# c8t61.net
KiCad netlist of a schematic drawn in Altium Designer
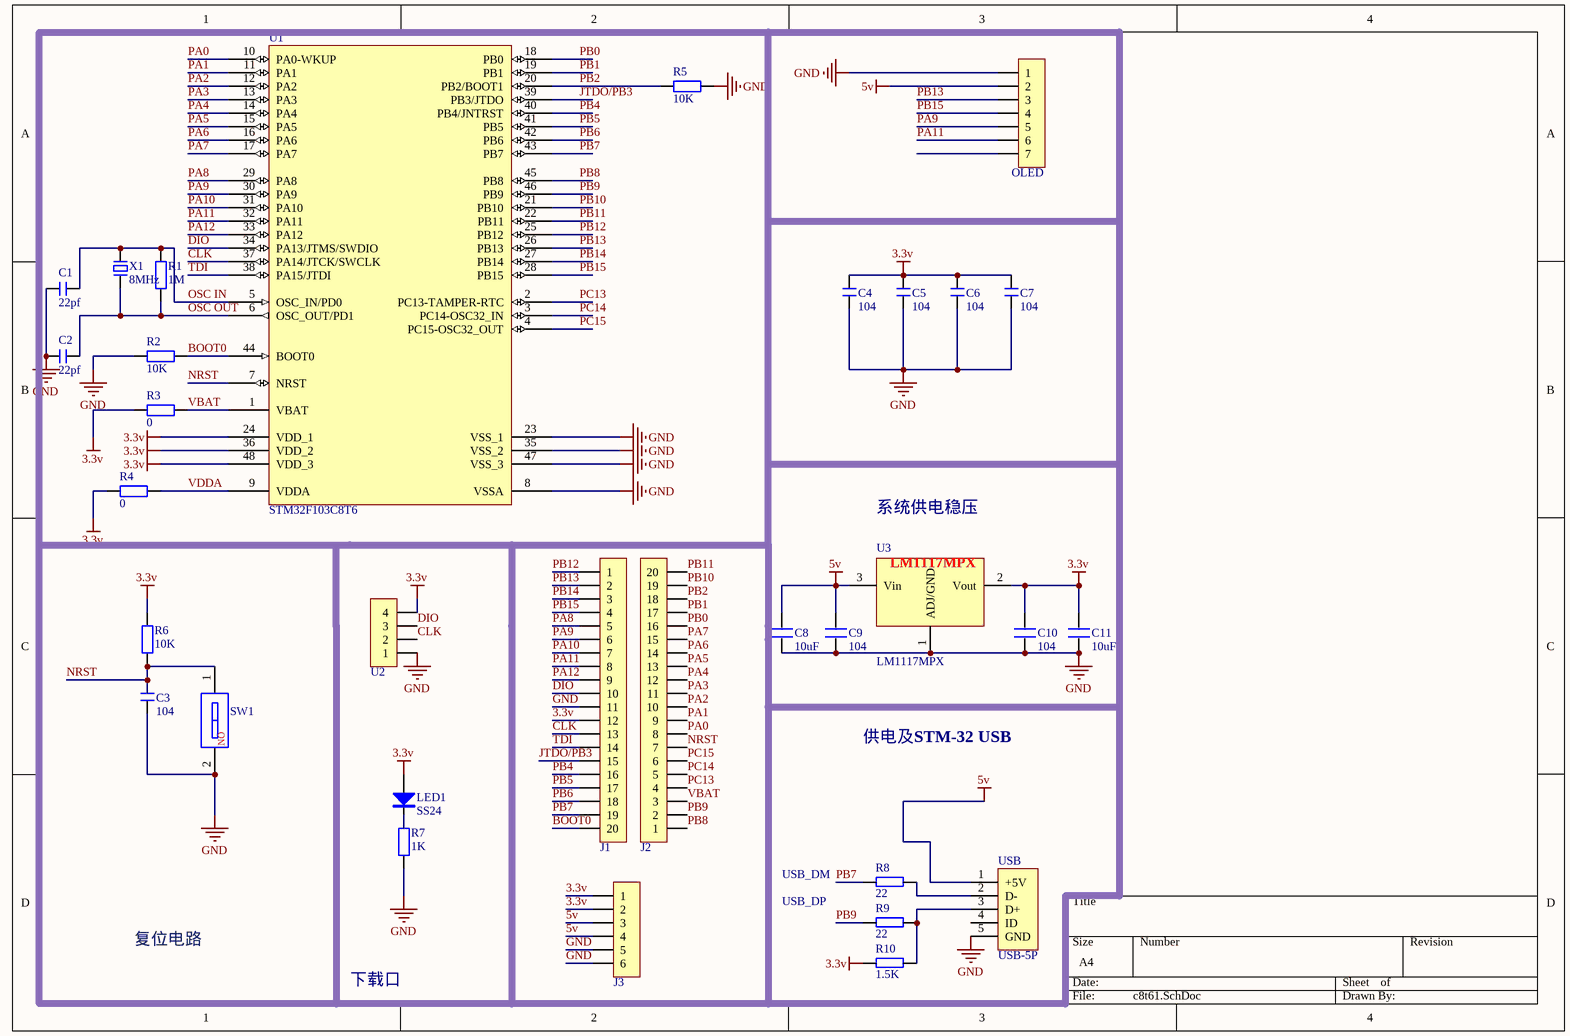
[diagram p0: c8t61.SchDoc]

(export (version "E")
  (design (tool "Eeschema 10.0.6"))
  (components
    (comp (ref "C1")
      (value "22pf")
      (footprint "C 0603")
      (description "无极性贴片电容")
      (fields (field (name "版权归属") "源创客"))
      (libsource (lib "电阻-电容-电感") (part "C"))
    )
    (comp (ref "C2")
      (value "22pf")
      (footprint "C 0603")
      (description "无极性贴片电容")
      (fields (field (name "版权归属") "源创客"))
      (libsource (lib "电阻-电容-电感") (part "C"))
    )
    (comp (ref "C3")
      (value "104")
      (footprint "C 0603")
      (description "无极性贴片电容")
      (fields (field (name "版权归属") "源创客"))
      (libsource (lib "电阻-电容-电感") (part "C"))
    )
    (comp (ref "C4")
      (value "104")
      (footprint "C 0603")
      (description "无极性贴片电容")
      (fields (field (name "版权归属") "源创客"))
      (libsource (lib "电阻-电容-电感") (part "C"))
    )
    (comp (ref "C5")
      (value "104")
      (footprint "C 0603")
      (description "无极性贴片电容")
      (fields (field (name "版权归属") "源创客"))
      (libsource (lib "电阻-电容-电感") (part "C"))
    )
    (comp (ref "C6")
      (value "104")
      (footprint "C 0603")
      (description "无极性贴片电容")
      (fields (field (name "版权归属") "源创客"))
      (libsource (lib "电阻-电容-电感") (part "C"))
    )
    (comp (ref "C7")
      (value "104")
      (footprint "C 0603")
      (description "无极性贴片电容")
      (fields (field (name "版权归属") "源创客"))
      (libsource (lib "电阻-电容-电感") (part "C"))
    )
    (comp (ref "C8") (value "10uF") (footprint "C 0805") (libsource (lib "战舰STM32开发板底板封装库") (part "C")))
    (comp (ref "C9") (value "104") (footprint "C 0805") (libsource (lib "战舰STM32开发板底板封装库") (part "C")))
    (comp (ref "C10") (value "104") (footprint "C 0805") (libsource (lib "战舰STM32开发板底板封装库") (part "C")))
    (comp (ref "C11") (value "10uF") (footprint "C 0805") (libsource (lib "战舰STM32开发板底板封装库") (part "C")))
    (comp (ref "J1")
      (value "HDR-1X20")
      (footprint "HDR-1X20")
      (description "20P接插件")
      (fields (field (name "版权归属") "源创客"))
      (libsource (lib "接插件") (part "Header 20"))
    )
    (comp (ref "J2")
      (value "HDR-1X20")
      (footprint "HDR-1X20")
      (description "20P接插件")
      (fields (field (name "版权归属") "源创客"))
      (libsource (lib "") (part "Header 20_1"))
    )
    (comp (ref "J3")
      (value "HDR-1X6")
      (footprint "HDR-1X6")
      (description "6P接插件")
      (fields (field (name "版权归属") "源创客"))
      (libsource (lib "接插件") (part "Header 6"))
    )
    (comp (ref "LED1")
      (value "SS24")
      (footprint "LED 1206G")
      (description "肖特基二极管")
      (fields (field (name "版权归属") "源创客"))
      (libsource (lib "二极管-整流桥") (part "SS24"))
    )
    (comp (ref "OLED")
      (value "HDR-1X7")
      (footprint "HDR-1X7")
      (description "7P接插件")
      (fields (field (name "版权归属") "源创客"))
      (libsource (lib "接插件") (part "Header 7"))
    )
    (comp (ref "R1")
      (value "1M")
      (footprint "R 0603")
      (description "贴片电阻")
      (fields (field (name "版权归属") "源创客"))
      (libsource (lib "电阻-电容-电感") (part "R"))
    )
    (comp (ref "R2")
      (value "10K")
      (footprint "R 0603")
      (description "贴片电阻")
      (fields (field (name "版权归属") "源创客"))
      (libsource (lib "电阻-电容-电感") (part "R"))
    )
    (comp (ref "R3")
      (value "0")
      (footprint "R 0603")
      (description "贴片电阻")
      (fields (field (name "版权归属") "源创客"))
      (libsource (lib "电阻-电容-电感") (part "R"))
    )
    (comp (ref "R4")
      (value "0")
      (footprint "R 0603")
      (description "贴片电阻")
      (fields (field (name "版权归属") "源创客"))
      (libsource (lib "电阻-电容-电感") (part "R"))
    )
    (comp (ref "R5")
      (value "10K")
      (footprint "R 0603")
      (description "贴片电阻")
      (fields (field (name "版权归属") "源创客"))
      (libsource (lib "电阻-电容-电感") (part "R"))
    )
    (comp (ref "R6")
      (value "10K")
      (footprint "R 0603")
      (description "贴片电阻")
      (fields (field (name "版权归属") "源创客"))
      (libsource (lib "电阻-电容-电感") (part "R"))
    )
    (comp (ref "R7")
      (value "1K")
      (footprint "R 0603")
      (description "贴片电阻")
      (fields (field (name "版权归属") "源创客"))
      (libsource (lib "电阻-电容-电感") (part "R"))
    )
    (comp (ref "R8") (value "22") (footprint "R 0805") (libsource (lib "战舰STM32开发板底板封装库") (part "R")))
    (comp (ref "R9") (value "22") (footprint "R 0805") (libsource (lib "战舰STM32开发板底板封装库") (part "R")))
    (comp (ref "R10") (value "1.5K") (footprint "R 0805") (libsource (lib "战舰STM32开发板底板封装库") (part "R")))
    (comp (ref "SW1")
      (value "CSW-1P")
      (footprint "TSW SMD-3*6*5")
      (description "2路编码开关")
      (fields (field (name "版权归属") "源创客"))
      (libsource (lib "按键-开关") (part "CSW-1P"))
    )
    (comp (ref "U1")
      (value "STM32F103C8T6")
      (footprint "LQFP48 7X7_M")
      (description "Flaah:64/RAM:20/IO:36")
      (fields (field (name "版权归属") "源创客"))
      (libsource (lib "STM32系列单片机") (part "STM32F103C8T6"))
    )
    (comp (ref "U2")
      (value "HDR-1X4")
      (footprint "HDR-1X4")
      (description "4P接插件")
      (fields (field (name "版权归属") "源创客"))
      (libsource (lib "接插件") (part "Header 4"))
    )
    (comp (ref "U3")
      (value "LM1117MPX")
      (footprint "SOT-223-4")
      (description "NS 800mA Low-Dropout Linear Regulator")
      (libsource (lib "电源管理") (part "LM1117MPX"))
    )
    (comp (ref "USB")
      (value "USB-5P")
      (footprint "USB-MICRO_A")
      (description "微型USB母座")
      (fields (field (name "版权归属") "源创客"))
      (libsource (lib "接口类") (part "USB-5P"))
    )
    (comp (ref "X1")
      (value "8MHz")
      (footprint "SMD5032-2")
      (description "2脚晶振")
      (fields (field (name "版权归属") "源创客"))
      (libsource (lib "保险丝-晶振") (part "XTAL-2"))
    )
  )
  (nets
    (net (code "1") (name "/BOOT0") (class "Default")
      (node (ref "J1") (pin "20") (pinfunction "20_20") (pintype "passive"))
      (node (ref "R2") (pin "1") (pinfunction "1_1") (pintype "passive"))
      (node (ref "U1") (pin "44") (pinfunction "BOOT0_44") (pintype "input"))
    )
    (net (code "2") (name "/CLK") (class "Default")
      (node (ref "J1") (pin "13") (pinfunction "13_13") (pintype "passive"))
      (node (ref "U1") (pin "37") (pinfunction "PA14/JTCK/SWCLK_37") (pintype "bidirectional"))
      (node (ref "U2") (pin "2") (pinfunction "2_2") (pintype "passive"))
    )
    (net (code "3") (name "/DIO") (class "Default")
      (node (ref "J1") (pin "10") (pinfunction "10_10") (pintype "passive"))
      (node (ref "U1") (pin "34") (pinfunction "PA13/JTMS/SWDIO_34") (pintype "bidirectional"))
      (node (ref "U2") (pin "3") (pinfunction "3_3") (pintype "passive"))
    )
    (net (code "4") (name "/JTDO{slash}PB3") (class "Default")
      (node (ref "J1") (pin "15") (pinfunction "15_15") (pintype "passive"))
      (node (ref "U1") (pin "39") (pinfunction "PB3/JTDO_39") (pintype "bidirectional"))
    )
    (net (code "5") (name "/NRST") (class "Default")
      (node (ref "C3") (pin "2") (pinfunction "2_2") (pintype "passive"))
      (node (ref "J2") (pin "7") (pinfunction "7_7") (pintype "passive"))
      (node (ref "R6") (pin "2") (pinfunction "2_2") (pintype "passive"))
      (node (ref "SW1") (pin "1") (pinfunction "1_1") (pintype "passive"))
      (node (ref "U1") (pin "7") (pinfunction "NRST_7") (pintype "bidirectional"))
    )
    (net (code "6") (name "/OSC IN") (class "Default")
      (node (ref "C1") (pin "2") (pinfunction "2_2") (pintype "passive"))
      (node (ref "R1") (pin "2") (pinfunction "2_2") (pintype "passive"))
      (node (ref "U1") (pin "5") (pinfunction "OSC_IN/PD0_5") (pintype "input"))
      (node (ref "X1") (pin "2") (pinfunction "2_2") (pintype "passive"))
    )
    (net (code "7") (name "/OSC OUT") (class "Default")
      (node (ref "C2") (pin "2") (pinfunction "2_2") (pintype "passive"))
      (node (ref "R1") (pin "1") (pinfunction "1_1") (pintype "passive"))
      (node (ref "U1") (pin "6") (pinfunction "OSC_OUT/PD1_6") (pintype "output"))
      (node (ref "X1") (pin "1") (pinfunction "1_1") (pintype "passive"))
    )
    (net (code "8") (name "/PA0") (class "Default")
      (node (ref "J2") (pin "8") (pinfunction "8_8") (pintype "passive"))
      (node (ref "U1") (pin "10") (pinfunction "PA0-WKUP_10") (pintype "bidirectional"))
    )
    (net (code "9") (name "/PA1") (class "Default")
      (node (ref "J2") (pin "9") (pinfunction "9_9") (pintype "passive"))
      (node (ref "U1") (pin "11") (pinfunction "PA1_11") (pintype "bidirectional"))
    )
    (net (code "10") (name "/PA2") (class "Default")
      (node (ref "J2") (pin "10") (pinfunction "10_10") (pintype "passive"))
      (node (ref "U1") (pin "12") (pinfunction "PA2_12") (pintype "bidirectional"))
    )
    (net (code "11") (name "/PA3") (class "Default")
      (node (ref "J2") (pin "11") (pinfunction "11_11") (pintype "passive"))
      (node (ref "U1") (pin "13") (pinfunction "PA3_13") (pintype "bidirectional"))
    )
    (net (code "12") (name "/PA4") (class "Default")
      (node (ref "J2") (pin "12") (pinfunction "12_12") (pintype "passive"))
      (node (ref "U1") (pin "14") (pinfunction "PA4_14") (pintype "bidirectional"))
    )
    (net (code "13") (name "/PA5") (class "Default")
      (node (ref "J2") (pin "13") (pinfunction "13_13") (pintype "passive"))
      (node (ref "U1") (pin "15") (pinfunction "PA5_15") (pintype "bidirectional"))
    )
    (net (code "14") (name "/PA6") (class "Default")
      (node (ref "J2") (pin "14") (pinfunction "14_14") (pintype "passive"))
      (node (ref "U1") (pin "16") (pinfunction "PA6_16") (pintype "bidirectional"))
    )
    (net (code "15") (name "/PA7") (class "Default")
      (node (ref "J2") (pin "15") (pinfunction "15_15") (pintype "passive"))
      (node (ref "U1") (pin "17") (pinfunction "PA7_17") (pintype "bidirectional"))
    )
    (net (code "16") (name "/PA8") (class "Default")
      (node (ref "J1") (pin "5") (pinfunction "5_5") (pintype "passive"))
      (node (ref "U1") (pin "29") (pinfunction "PA8_29") (pintype "bidirectional"))
    )
    (net (code "17") (name "/PA9") (class "Default")
      (node (ref "J1") (pin "6") (pinfunction "6_6") (pintype "passive"))
      (node (ref "OLED") (pin "5") (pinfunction "5_5") (pintype "passive"))
      (node (ref "U1") (pin "30") (pinfunction "PA9_30") (pintype "bidirectional"))
    )
    (net (code "18") (name "/PA10") (class "Default")
      (node (ref "J1") (pin "7") (pinfunction "7_7") (pintype "passive"))
      (node (ref "U1") (pin "31") (pinfunction "PA10_31") (pintype "bidirectional"))
    )
    (net (code "19") (name "/PA11") (class "Default")
      (node (ref "J1") (pin "8") (pinfunction "8_8") (pintype "passive"))
      (node (ref "OLED") (pin "6") (pinfunction "6_6") (pintype "passive"))
      (node (ref "U1") (pin "32") (pinfunction "PA11_32") (pintype "bidirectional"))
    )
    (net (code "20") (name "/PA12") (class "Default")
      (node (ref "J1") (pin "9") (pinfunction "9_9") (pintype "passive"))
      (node (ref "U1") (pin "33") (pinfunction "PA12_33") (pintype "bidirectional"))
    )
    (net (code "21") (name "/PB0") (class "Default")
      (node (ref "J2") (pin "16") (pinfunction "16_16") (pintype "passive"))
      (node (ref "U1") (pin "18") (pinfunction "PB0_18") (pintype "bidirectional"))
    )
    (net (code "22") (name "/PB1") (class "Default")
      (node (ref "J2") (pin "17") (pinfunction "17_17") (pintype "passive"))
      (node (ref "U1") (pin "19") (pinfunction "PB1_19") (pintype "bidirectional"))
    )
    (net (code "23") (name "/PB2") (class "Default")
      (node (ref "J2") (pin "18") (pinfunction "18_18") (pintype "passive"))
      (node (ref "R5") (pin "2") (pinfunction "2_2") (pintype "passive"))
      (node (ref "U1") (pin "20") (pinfunction "PB2/BOOT1_20") (pintype "bidirectional"))
    )
    (net (code "24") (name "/PB4") (class "Default")
      (node (ref "J1") (pin "16") (pinfunction "16_16") (pintype "passive"))
      (node (ref "U1") (pin "40") (pinfunction "PB4/JNTRST_40") (pintype "bidirectional"))
    )
    (net (code "25") (name "/PB5") (class "Default")
      (node (ref "J1") (pin "17") (pinfunction "17_17") (pintype "passive"))
      (node (ref "U1") (pin "41") (pinfunction "PB5_41") (pintype "bidirectional"))
    )
    (net (code "26") (name "/PB6") (class "Default")
      (node (ref "J1") (pin "18") (pinfunction "18_18") (pintype "passive"))
      (node (ref "U1") (pin "42") (pinfunction "PB6_42") (pintype "bidirectional"))
    )
    (net (code "27") (name "/PB7") (class "Default")
      (node (ref "J1") (pin "19") (pinfunction "19_19") (pintype "passive"))
      (node (ref "R8") (pin "2") (pintype "passive"))
      (node (ref "U1") (pin "43") (pinfunction "PB7_43") (pintype "bidirectional"))
    )
    (net (code "28") (name "/PB8") (class "Default")
      (node (ref "J2") (pin "1") (pinfunction "1_1") (pintype "passive"))
      (node (ref "U1") (pin "45") (pinfunction "PB8_45") (pintype "bidirectional"))
    )
    (net (code "29") (name "/PB9") (class "Default")
      (node (ref "J2") (pin "2") (pinfunction "2_2") (pintype "passive"))
      (node (ref "R9") (pin "2") (pintype "passive"))
      (node (ref "U1") (pin "46") (pinfunction "PB9_46") (pintype "bidirectional"))
    )
    (net (code "30") (name "/PB10") (class "Default")
      (node (ref "J2") (pin "19") (pinfunction "19_19") (pintype "passive"))
      (node (ref "U1") (pin "21") (pinfunction "PB10_21") (pintype "bidirectional"))
    )
    (net (code "31") (name "/PB11") (class "Default")
      (node (ref "J2") (pin "20") (pinfunction "20_20") (pintype "passive"))
      (node (ref "U1") (pin "22") (pinfunction "PB11_22") (pintype "bidirectional"))
    )
    (net (code "32") (name "/PB12") (class "Default")
      (node (ref "J1") (pin "1") (pinfunction "1_1") (pintype "passive"))
      (node (ref "U1") (pin "25") (pinfunction "PB12_25") (pintype "bidirectional"))
    )
    (net (code "33") (name "/PB13") (class "Default")
      (node (ref "J1") (pin "2") (pinfunction "2_2") (pintype "passive"))
      (node (ref "OLED") (pin "3") (pinfunction "3_3") (pintype "passive"))
      (node (ref "U1") (pin "26") (pinfunction "PB13_26") (pintype "bidirectional"))
    )
    (net (code "34") (name "/PB14") (class "Default")
      (node (ref "J1") (pin "3") (pinfunction "3_3") (pintype "passive"))
      (node (ref "U1") (pin "27") (pinfunction "PB14_27") (pintype "bidirectional"))
    )
    (net (code "35") (name "/PB15") (class "Default")
      (node (ref "J1") (pin "4") (pinfunction "4_4") (pintype "passive"))
      (node (ref "OLED") (pin "4") (pinfunction "4_4") (pintype "passive"))
      (node (ref "U1") (pin "28") (pinfunction "PB15_28") (pintype "bidirectional"))
    )
    (net (code "36") (name "/PC13") (class "Default")
      (node (ref "J2") (pin "4") (pinfunction "4_4") (pintype "passive"))
      (node (ref "U1") (pin "2") (pinfunction "PC13-TAMPER-RTC_2") (pintype "bidirectional"))
    )
    (net (code "37") (name "/PC14") (class "Default")
      (node (ref "J2") (pin "5") (pinfunction "5_5") (pintype "passive"))
      (node (ref "U1") (pin "3") (pinfunction "PC14-OSC32_IN_3") (pintype "bidirectional"))
    )
    (net (code "38") (name "/PC15") (class "Default")
      (node (ref "J2") (pin "6") (pinfunction "6_6") (pintype "passive"))
      (node (ref "U1") (pin "4") (pinfunction "PC15-OSC32_OUT_4") (pintype "bidirectional"))
    )
    (net (code "39") (name "/TDI") (class "Default")
      (node (ref "J1") (pin "14") (pinfunction "14_14") (pintype "passive"))
      (node (ref "U1") (pin "38") (pinfunction "PA15/JTDI_38") (pintype "bidirectional"))
    )
    (net (code "40") (name "/VBAT") (class "Default")
      (node (ref "J2") (pin "3") (pinfunction "3_3") (pintype "passive"))
      (node (ref "R3") (pin "1") (pinfunction "1_1") (pintype "passive"))
      (node (ref "U1") (pin "1") (pinfunction "VBAT_1") (pintype "power_in"))
    )
    (net (code "41") (name "/VDDA") (class "Default")
      (node (ref "R4") (pin "2") (pinfunction "2_2") (pintype "passive"))
      (node (ref "U1") (pin "9") (pinfunction "VDDA_9") (pintype "power_in"))
    )
    (net (code "42") (name "3.3v") (class "Default")
      (node (ref "C10") (pin "2") (pintype "passive"))
      (node (ref "C11") (pin "2") (pintype "passive"))
      (node (ref "C4") (pin "2") (pinfunction "2_2") (pintype "passive"))
      (node (ref "C5") (pin "2") (pinfunction "2_2") (pintype "passive"))
      (node (ref "C6") (pin "2") (pinfunction "2_2") (pintype "passive"))
      (node (ref "C7") (pin "2") (pinfunction "2_2") (pintype "passive"))
      (node (ref "J1") (pin "12") (pinfunction "12_12") (pintype "passive"))
      (node (ref "J3") (pin "1") (pinfunction "1_1") (pintype "passive"))
      (node (ref "J3") (pin "2") (pinfunction "2_2") (pintype "passive"))
      (node (ref "LED1") (pin "1") (pinfunction "A_1") (pintype "passive"))
      (node (ref "R10") (pin "2") (pintype "passive"))
      (node (ref "R3") (pin "2") (pinfunction "2_2") (pintype "passive"))
      (node (ref "R4") (pin "1") (pinfunction "1_1") (pintype "passive"))
      (node (ref "R6") (pin "1") (pinfunction "1_1") (pintype "passive"))
      (node (ref "U1") (pin "24") (pinfunction "VDD_1_24") (pintype "power_in"))
      (node (ref "U1") (pin "36") (pinfunction "VDD_2_36") (pintype "power_in"))
      (node (ref "U1") (pin "48") (pinfunction "VDD_3_48") (pintype "power_in"))
      (node (ref "U2") (pin "4") (pinfunction "4_4") (pintype "passive"))
      (node (ref "U3") (pin "2") (pinfunction "Vout_2") (pintype "passive"))
    )
    (net (code "43") (name "5v") (class "Default")
      (node (ref "C8") (pin "2") (pintype "passive"))
      (node (ref "C9") (pin "2") (pintype "passive"))
      (node (ref "J3") (pin "3") (pinfunction "3_3") (pintype "passive"))
      (node (ref "J3") (pin "4") (pinfunction "4_4") (pintype "passive"))
      (node (ref "OLED") (pin "2") (pinfunction "2_2") (pintype "passive"))
      (node (ref "U3") (pin "3") (pinfunction "Vin_3") (pintype "passive"))
      (node (ref "USB") (pin "1") (pinfunction "+5V_1") (pintype "passive"))
    )
    (net (code "44") (name "GND") (class "Default")
      (node (ref "C1") (pin "1") (pinfunction "1_1") (pintype "passive"))
      (node (ref "C10") (pin "1") (pintype "passive"))
      (node (ref "C11") (pin "1") (pintype "passive"))
      (node (ref "C2") (pin "1") (pinfunction "1_1") (pintype "passive"))
      (node (ref "C3") (pin "1") (pinfunction "1_1") (pintype "passive"))
      (node (ref "C4") (pin "1") (pinfunction "1_1") (pintype "passive"))
      (node (ref "C5") (pin "1") (pinfunction "1_1") (pintype "passive"))
      (node (ref "C6") (pin "1") (pinfunction "1_1") (pintype "passive"))
      (node (ref "C7") (pin "1") (pinfunction "1_1") (pintype "passive"))
      (node (ref "C8") (pin "1") (pintype "passive"))
      (node (ref "C9") (pin "1") (pintype "passive"))
      (node (ref "J1") (pin "11") (pinfunction "11_11") (pintype "passive"))
      (node (ref "J3") (pin "5") (pinfunction "5_5") (pintype "passive"))
      (node (ref "J3") (pin "6") (pinfunction "6_6") (pintype "passive"))
      (node (ref "OLED") (pin "1") (pinfunction "1_1") (pintype "passive"))
      (node (ref "R2") (pin "2") (pinfunction "2_2") (pintype "passive"))
      (node (ref "R5") (pin "1") (pinfunction "1_1") (pintype "passive"))
      (node (ref "R7") (pin "2") (pinfunction "2_2") (pintype "passive"))
      (node (ref "SW1") (pin "2") (pinfunction "2_2") (pintype "passive"))
      (node (ref "U1") (pin "23") (pinfunction "VSS_1_23") (pintype "power_in"))
      (node (ref "U1") (pin "35") (pinfunction "VSS_2_35") (pintype "power_in"))
      (node (ref "U1") (pin "47") (pinfunction "VSS_3_47") (pintype "power_in"))
      (node (ref "U1") (pin "8") (pinfunction "VSSA_8") (pintype "power_in"))
      (node (ref "U2") (pin "1") (pinfunction "1_1") (pintype "passive"))
      (node (ref "U3") (pin "1") (pinfunction "ADJ/GND_1") (pintype "passive"))
      (node (ref "USB") (pin "5") (pinfunction "GND_5") (pintype "passive"))
    )
    (net (code "45") (name "Net-(LED1-K)") (class "Default")
      (node (ref "LED1") (pin "2") (pinfunction "K_2") (pintype "passive"))
      (node (ref "R7") (pin "1") (pinfunction "1_1") (pintype "passive"))
    )
    (net (code "46") (name "Net-(USB-D+)") (class "Default")
      (node (ref "R10") (pin "1") (pintype "passive"))
      (node (ref "R9") (pin "1") (pintype "passive"))
      (node (ref "USB") (pin "3") (pinfunction "D+_3") (pintype "passive"))
    )
    (net (code "47") (name "Net-(USB-D-)") (class "Default")
      (node (ref "R8") (pin "1") (pintype "passive"))
      (node (ref "USB") (pin "2") (pinfunction "D-_2") (pintype "passive"))
    )
    (net (code "48") (name "unconnected-(OLED-Pad7)") (class "Default")
      (node (ref "OLED") (pin "7") (pinfunction "7_7") (pintype "passive"))
    )
    (net (code "49") (name "unconnected-(USB-ID-Pad4)") (class "Default")
      (node (ref "USB") (pin "4") (pinfunction "ID_4") (pintype "passive"))
    )
  )
)
